# ELRS.net
KiCad netlist of a schematic drawn in Altium Designer
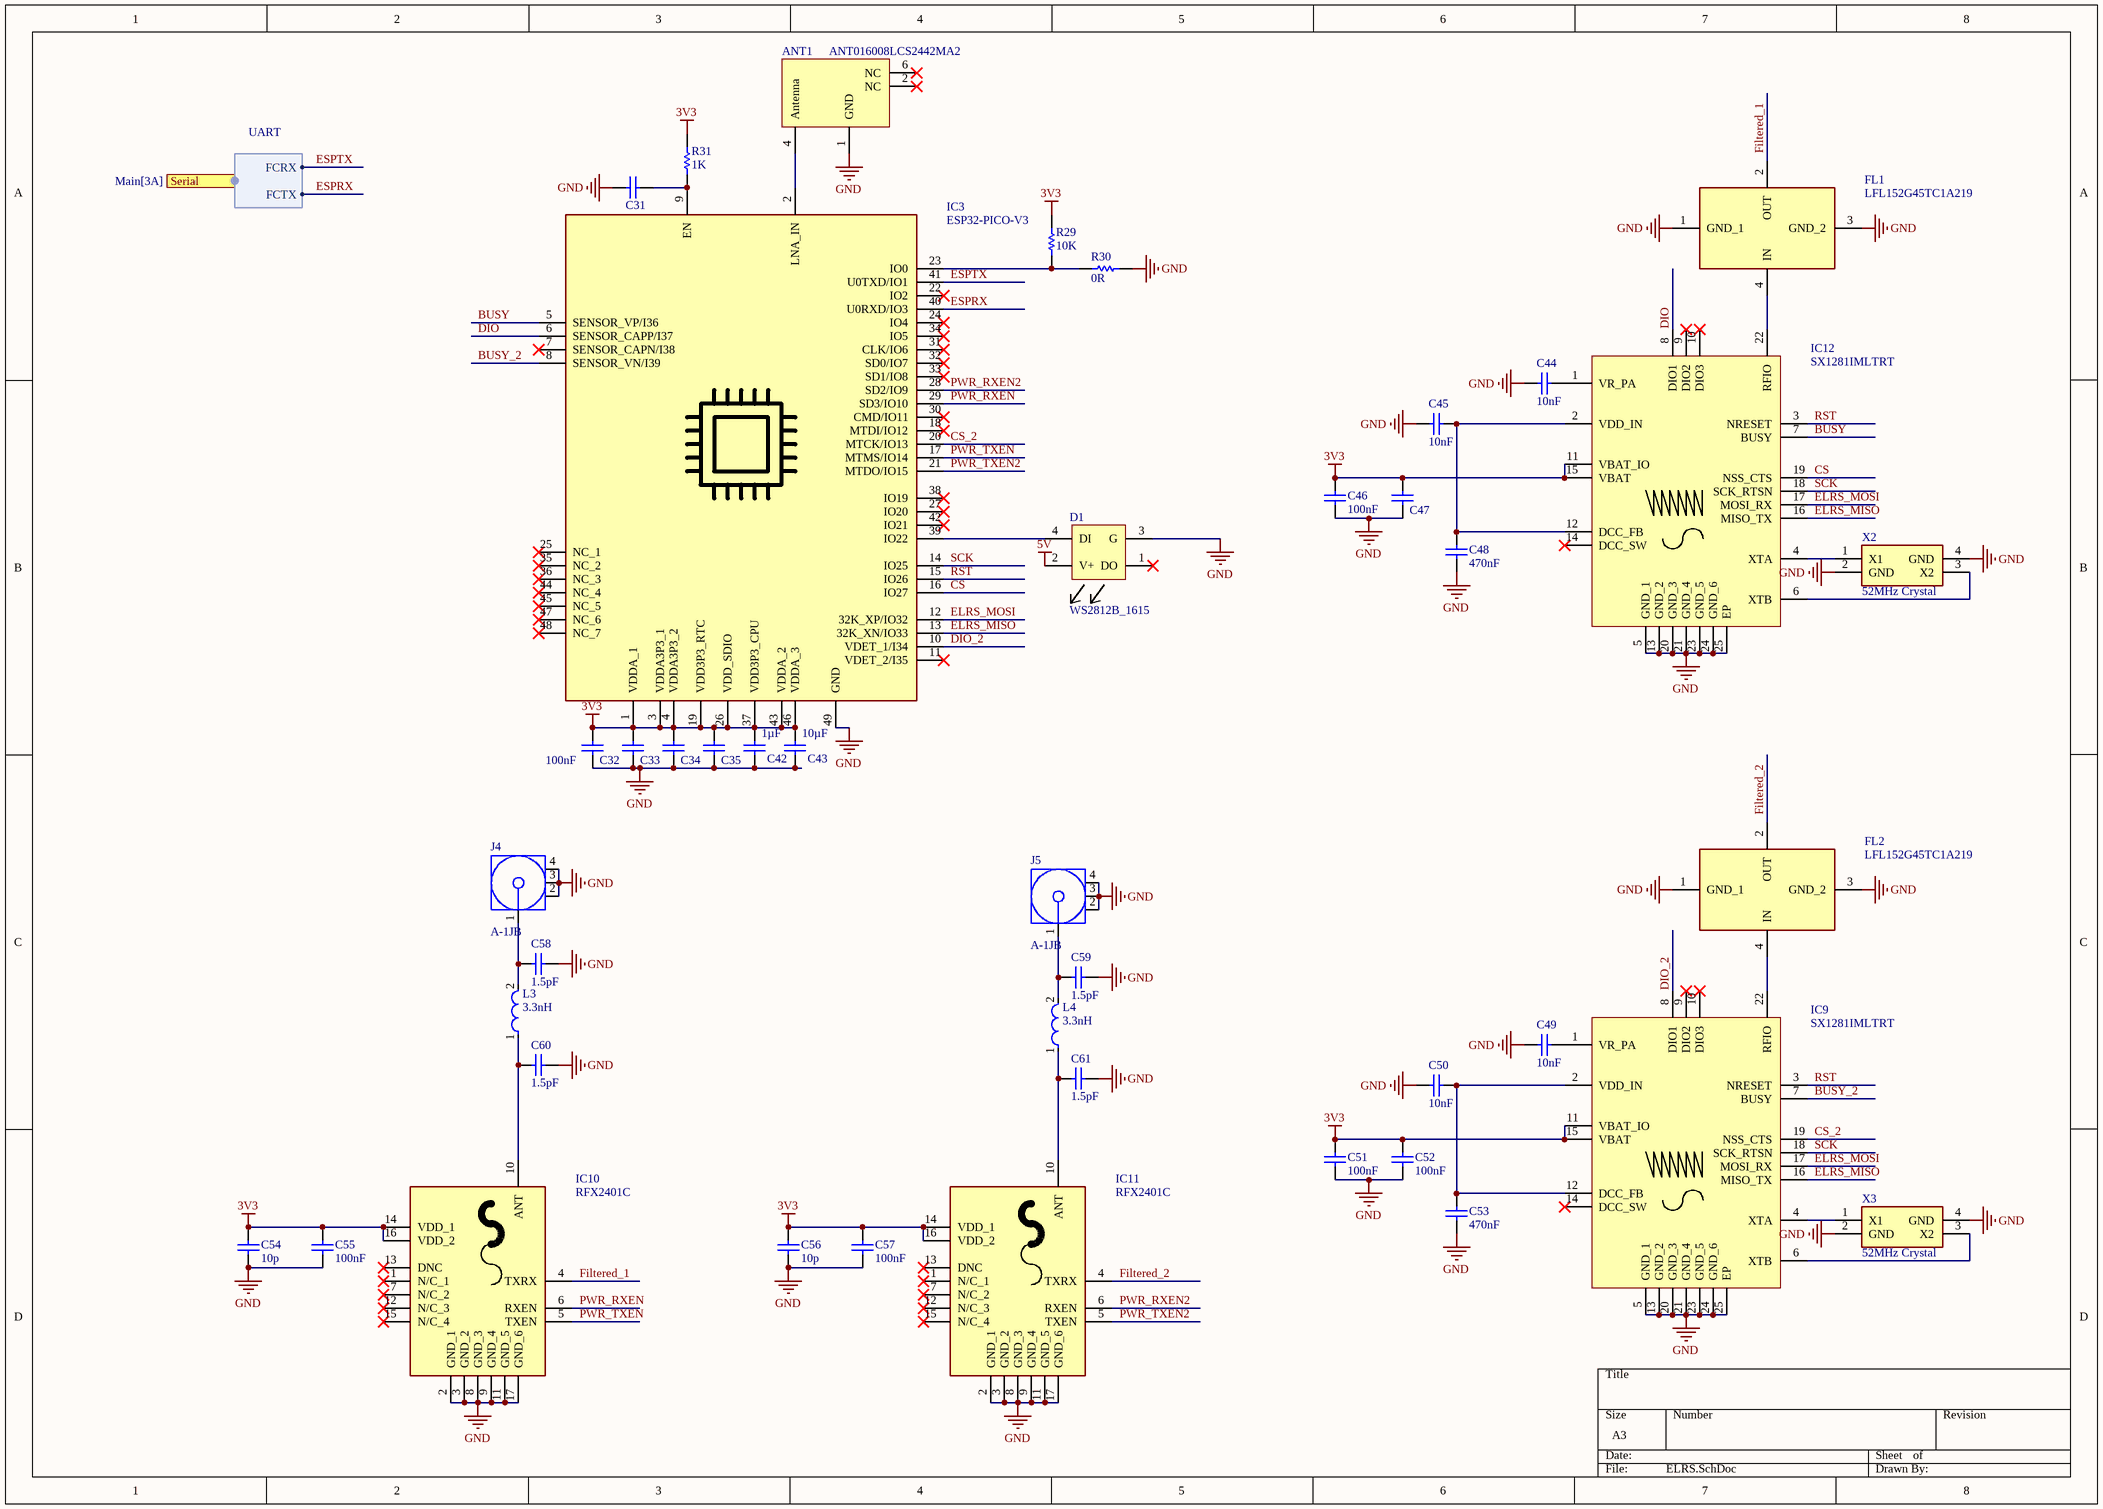
[diagram p0: ELRS.SchDoc]

(export (version "E")
  (design (tool "Eeschema 10.0.6"))
  (components
    (comp (ref "ANT1")
      (value "ANT016008LCS2442MA2")
      (footprint "Custom Components:ANT016008LCS2442MA2")
      (description "Antenna")
      (fields (field (name "MOUSER PART NUMBER") "810-ANT168LCS2442MA2"))
      (libsource (lib "Custom Components") (part "ANT016008LCS2442MA2"))
    )
    (comp (ref "C31")
      (value "100nF")
      (footprint "WCAP-CSGP_0603_L1.6W0.8H0.8_Reflow")
      (description "WCAP-CSGP Multilayer Ceramic Chip Capacitor, General Purpose, size 0603, X7R, 100nF, 50VDC")
      (fields
        (field (name "MANUFACTURER PART NUMBER") "885012206095")
        (field (name "MANUFACTURER") "Wurth Elektronik")
      )
      (libsource (lib "Altium_WCAP-CSGP (rev22f)") (part "885012206095"))
    )
    (comp (ref "C32")
      (value "100nF")
      (footprint "WCAP-CSGP_0603_L1.6W0.8H0.8_Reflow")
      (description "WCAP-CSGP Multilayer Ceramic Chip Capacitor, General Purpose, size 0603, X7R, 100nF, 50VDC")
      (fields
        (field (name "MANUFACTURER PART NUMBER") "885012206095")
        (field (name "MANUFACTURER") "Wurth Elektronik")
      )
      (libsource (lib "Altium_WCAP-CSGP (rev22f)") (part "885012206095"))
    )
    (comp (ref "C33")
      (value "100nF")
      (footprint "WCAP-CSGP_0603_L1.6W0.8H0.8_Reflow")
      (description "WCAP-CSGP Multilayer Ceramic Chip Capacitor, General Purpose, size 0603, X7R, 100nF, 50VDC")
      (fields
        (field (name "MANUFACTURER PART NUMBER") "885012206095")
        (field (name "MANUFACTURER") "Wurth Elektronik")
      )
      (libsource (lib "Altium_WCAP-CSGP (rev22f)") (part "885012206095"))
    )
    (comp (ref "C34")
      (value "100nF")
      (footprint "WCAP-CSGP_0603_L1.6W0.8H0.8_Reflow")
      (description "WCAP-CSGP Multilayer Ceramic Chip Capacitor, General Purpose, size 0603, X7R, 100nF, 50VDC")
      (fields
        (field (name "MANUFACTURER PART NUMBER") "885012206095")
        (field (name "MANUFACTURER") "Wurth Elektronik")
      )
      (libsource (lib "Altium_WCAP-CSGP (rev22f)") (part "885012206095"))
    )
    (comp (ref "C35")
      (value "100nF")
      (footprint "WCAP-CSGP_0603_L1.6W0.8H0.8_Reflow")
      (description "WCAP-CSGP Multilayer Ceramic Chip Capacitor, General Purpose, size 0603, X7R, 100nF, 50VDC")
      (fields
        (field (name "MANUFACTURER PART NUMBER") "885012206095")
        (field (name "MANUFACTURER") "Wurth Elektronik")
      )
      (libsource (lib "Altium_WCAP-CSGP (rev22f)") (part "885012206095"))
    )
    (comp (ref "C42")
      (value "1µF")
      (footprint "WCAP-CSGP_0603_L1.6W0.8H0.8_Reflow")
      (description "WCAP-CSGP Multilayer Ceramic Chip Capacitor, General Purpose, size 0603, X7R, 1µF, 25VDC")
      (fields
        (field (name "MANUFACTURER PART NUMBER") "885012206076")
        (field (name "MANUFACTURER") "Wurth Elektronik")
      )
      (libsource (lib "Altium_WCAP-CSGP (rev22f)") (part "885012206076"))
    )
    (comp (ref "C43")
      (value "10µF")
      (footprint "WCAP-CSGP_0603_L1.6W0.8H0.8_Reflow")
      (description "WCAP-CSGP Multilayer Ceramic Chip Capacitor, General Purpose, size 0603, X5R, 10µF, 25VDC")
      (fields
        (field (name "MANUFACTURER PART NUMBER") "885012106031")
        (field (name "MANUFACTURER") "Wurth Elektronik")
      )
      (libsource (lib "Altium_WCAP-CSGP (rev22f)") (part "885012106031"))
    )
    (comp (ref "C44")
      (value "10nF")
      (footprint "0402 cap")
      (libsource (lib "Custom Components") (part "Capacitor 0402 100nF"))
    )
    (comp (ref "C45")
      (value "10nF")
      (footprint "0402 cap")
      (libsource (lib "Custom Components") (part "Capacitor 0402 100nF"))
    )
    (comp (ref "C46")
      (value "100nF")
      (footprint "0402 cap")
      (libsource (lib "Custom Components") (part "Capacitor 0402 100nF"))
    )
    (comp (ref "C47")
      (value "100nF")
      (footprint "WCAP-CSGP_0603_L1.6W0.8H0.8_Reflow")
      (description "WCAP-CSGP Multilayer Ceramic Chip Capacitor, General Purpose, size 0603, X7R, 100nF, 50VDC")
      (fields
        (field (name "MANUFACTURER PART NUMBER") "885012206095")
        (field (name "MANUFACTURER") "Wurth Elektronik")
      )
      (libsource (lib "Altium_WCAP-CSGP (rev22f)") (part "885012206095"))
    )
    (comp (ref "C48")
      (value "470nF")
      (footprint "0402 cap")
      (libsource (lib "Custom Components") (part "Capacitor 0402 100nF"))
    )
    (comp (ref "C49")
      (value "10nF")
      (footprint "0402 cap")
      (libsource (lib "Custom Components") (part "Capacitor 0402 100nF"))
    )
    (comp (ref "C50")
      (value "10nF")
      (footprint "0402 cap")
      (libsource (lib "Custom Components") (part "Capacitor 0402 100nF"))
    )
    (comp (ref "C51")
      (value "100nF")
      (footprint "0402 cap")
      (libsource (lib "Custom Components") (part "Capacitor 0402 100nF"))
    )
    (comp (ref "C52")
      (value "100nF")
      (footprint "0402 cap")
      (libsource (lib "Custom Components") (part "Capacitor 0402 100nF"))
    )
    (comp (ref "C53")
      (value "470nF")
      (footprint "0402 cap")
      (libsource (lib "Custom Components") (part "Capacitor 0402 100nF"))
    )
    (comp (ref "C54")
      (value "10p")
      (footprint "0402 cap")
      (libsource (lib "Custom Components") (part "Capacitor 0402 100nF"))
    )
    (comp (ref "C55")
      (value "100nF")
      (footprint "0402 cap")
      (libsource (lib "Custom Components") (part "Capacitor 0402 100nF"))
    )
    (comp (ref "C56")
      (value "10p")
      (footprint "0402 cap")
      (libsource (lib "Custom Components") (part "Capacitor 0402 100nF"))
    )
    (comp (ref "C57")
      (value "100nF")
      (footprint "0402 cap")
      (libsource (lib "Custom Components") (part "Capacitor 0402 100nF"))
    )
    (comp (ref "C58")
      (value "1.5pF")
      (footprint "0402 cap")
      (description "CL05C1R5BB5NNNC")
      (libsource (lib "Custom Components") (part "Capacitor 0402 100nF"))
    )
    (comp (ref "C59")
      (value "1.5pF")
      (footprint "0402 cap")
      (description "CL05C1R5BB5NNNC")
      (libsource (lib "Custom Components") (part "Capacitor 0402 100nF"))
    )
    (comp (ref "C60")
      (value "1.5pF")
      (footprint "0402 cap")
      (description "CL05C1R5BB5NNNC")
      (libsource (lib "Custom Components") (part "Capacitor 0402 100nF"))
    )
    (comp (ref "C61")
      (value "1.5pF")
      (footprint "0402 cap")
      (description "CL05C1R5BB5NNNC")
      (libsource (lib "Custom Components") (part "Capacitor 0402 100nF"))
    )
    (comp (ref "D1")
      (value "WS2812B_1615")
      (footprint "WS2812B_1615")
      (description "XINGLIGHT XL-1615RGBC-WS2812B")
      (libsource (lib "Custom Components") (part "WS2812B_1615"))
    )
    (comp (ref "FL1")
      (value "LFL152G45TC1A219")
      (footprint "Custom Components:LFL152G45TC1A219")
      (description "Filter")
      (fields (field (name "MOUSER PART NUMBER") "81-LFL152G45TC1A219"))
      (libsource (lib "*") (part "LFL152G45TC1A219"))
    )
    (comp (ref "FL2")
      (value "LFL152G45TC1A219")
      (footprint "Custom Components:LFL152G45TC1A219")
      (description "Filter")
      (fields (field (name "MOUSER PART NUMBER") "81-LFL152G45TC1A219"))
      (libsource (lib "*") (part "LFL152G45TC1A219"))
    )
    (comp (ref "IC3")
      (value "ESP32-PICO-V3")
      (footprint "Custom Components:ESP32PICOV3")
      (description "Integrated Circuit")
      (fields (field (name "MOUSER PART NUMBER") "356-ESP32-PICO-V3"))
      (libsource (lib "Custom Components") (part "ESP32-PICO-V3"))
    )
    (comp (ref "IC9")
      (value "SX1281IMLTRT")
      (footprint "Custom Components:QFN50P400X400X100-25N-D")
      (description "Integrated Circuit")
      (fields (field (name "MOUSER PART NUMBER") "947-SX1281IMLTRT"))
      (libsource (lib "Custom Components") (part "SX1281IMLTRT"))
    )
    (comp (ref "IC10")
      (value "RFX2401C")
      (footprint "Custom Components:QFN50P300X300X60-17N-D")
      (description "Integrated Circuit")
      (fields (field (name "MOUSER PART NUMBER") "477-RFX2401C"))
      (libsource (lib "Custom Components") (part "RFX2401C"))
    )
    (comp (ref "IC11")
      (value "RFX2401C")
      (footprint "Custom Components:QFN50P300X300X60-17N-D")
      (description "Integrated Circuit")
      (fields (field (name "MOUSER PART NUMBER") "477-RFX2401C"))
      (libsource (lib "Custom Components") (part "RFX2401C"))
    )
    (comp (ref "IC12")
      (value "SX1281IMLTRT")
      (footprint "Custom Components:QFN50P400X400X100-25N-D")
      (description "Integrated Circuit")
      (fields (field (name "MOUSER PART NUMBER") "947-SX1281IMLTRT"))
      (libsource (lib "Custom Components") (part "SX1281IMLTRT"))
    )
    (comp (ref "J4")
      (value "A-1JB")
      (footprint "AMPH-A-1JB_V")
      (description "AMC PCB Jack, 0 to 60 GHz, 60 V, -40 to 90 degC, 4-Pin SMD, RoHS, Tape and Reel")
      (fields (field (name "TOLERANCE") "10%"))
      (libsource (lib "Altium Content Vault") (part "CN-S-3F-RF4"))
    )
    (comp (ref "J5")
      (value "A-1JB")
      (footprint "AMPH-A-1JB_V")
      (description "AMC PCB Jack, 0 to 60 GHz, 60 V, -40 to 90 degC, 4-Pin SMD, RoHS, Tape and Reel")
      (fields (field (name "TOLERANCE") "10%"))
      (libsource (lib "Altium Content Vault") (part "CN-S-3F-RF4"))
    )
    (comp (ref "L3")
      (value "3.3nH")
      (footprint "FP-LQW15AN_00-W0_6-0_1-MFG")
      (description "MLG1005S3N3BT000")
      (libsource (lib "Altium Content Vault") (part "725321dda6339637d4d059423bc1c3c"))
    )
    (comp (ref "L4")
      (value "3.3nH")
      (footprint "FP-LQW15AN_00-W0_6-0_1-MFG")
      (description "MLG1005S3N3BT000")
      (libsource (lib "Altium Content Vault") (part "725321dda6339637d4d059423bc1c3c"))
    )
    (comp (ref "R29")
      (value "10K")
      (footprint "Custom Components:0402 resistor")
      (libsource (lib "Custom Components") (part "Resistor 0402 1K"))
    )
    (comp (ref "R30")
      (value "0R")
      (footprint "Custom Components:0402 resistor")
      (libsource (lib "Custom Components") (part "Resistor 0402 1K"))
    )
    (comp (ref "R31")
      (value "1K")
      (footprint "Custom Components:0402 resistor")
      (libsource (lib "Custom Components") (part "Resistor 0402 1K"))
    )
    (comp (ref "X2")
      (value "52MHz Crystal")
      (footprint "2016 Crystal")
      (description "HCI XC21M4-52.000-F10NNHPL")
      (libsource (lib "Custom Components") (part "HCI XC21M4-52.000"))
    )
    (comp (ref "X3")
      (value "52MHz Crystal")
      (footprint "2016 Crystal")
      (description "HCI XC21M4-52.000-F10NNHPL")
      (libsource (lib "Custom Components") (part "HCI XC21M4-52.000"))
    )
  )
  (nets
    (net (code "2") (name "/BUSY") (class "Default")
      (node (ref "IC12") (pin "7") (pinfunction "BUSY_7") (pintype "passive"))
      (node (ref "IC3") (pin "5") (pinfunction "SENSOR_VP/I36_5") (pintype "passive"))
    )
    (net (code "3") (name "/BUSY_2") (class "Default")
      (node (ref "IC3") (pin "8") (pinfunction "SENSOR_VN/I39_8") (pintype "passive"))
      (node (ref "IC9") (pin "7") (pinfunction "BUSY_7") (pintype "passive"))
    )
    (net (code "4") (name "/CS") (class "Default")
      (node (ref "IC12") (pin "19") (pinfunction "NSS_CTS_19") (pintype "passive"))
      (node (ref "IC3") (pin "16") (pinfunction "IO27_16") (pintype "passive"))
    )
    (net (code "5") (name "/CS_2") (class "Default")
      (node (ref "IC3") (pin "20") (pinfunction "MTCK/IO13_20") (pintype "passive"))
      (node (ref "IC9") (pin "19") (pinfunction "NSS_CTS_19") (pintype "passive"))
    )
    (net (code "6") (name "/DIO") (class "Default")
      (node (ref "IC12") (pin "8") (pinfunction "DIO1_8") (pintype "passive"))
      (node (ref "IC3") (pin "6") (pinfunction "SENSOR_CAPP/I37_6") (pintype "passive"))
    )
    (net (code "7") (name "/DIO_2") (class "Default")
      (node (ref "IC3") (pin "10") (pinfunction "VDET_1/I34_10") (pintype "passive"))
      (node (ref "IC9") (pin "8") (pinfunction "DIO1_8") (pintype "passive"))
    )
    (net (code "8") (name "/ELRS_MISO") (class "Default")
      (node (ref "IC12") (pin "16") (pinfunction "MISO_TX_16") (pintype "passive"))
      (node (ref "IC3") (pin "13") (pinfunction "32K_XN/IO33_13") (pintype "passive"))
      (node (ref "IC9") (pin "16") (pinfunction "MISO_TX_16") (pintype "passive"))
    )
    (net (code "9") (name "/ELRS_MOSI") (class "Default")
      (node (ref "IC12") (pin "17") (pinfunction "MOSI_RX_17") (pintype "passive"))
      (node (ref "IC3") (pin "12") (pinfunction "32K_XP/IO32_12") (pintype "passive"))
      (node (ref "IC9") (pin "17") (pinfunction "MOSI_RX_17") (pintype "passive"))
    )
    (net (code "10") (name "/ESPRX") (class "Default")
      (node (ref "IC3") (pin "40") (pinfunction "U0RXD/IO3_40") (pintype "passive"))
    )
    (net (code "11") (name "/ESPTX") (class "Default")
      (node (ref "IC3") (pin "41") (pinfunction "U0TXD/IO1_41") (pintype "passive"))
    )
    (net (code "12") (name "/Filtered_1") (class "Default")
      (node (ref "FL1") (pin "2") (pinfunction "OUT_2") (pintype "passive"))
      (node (ref "IC10") (pin "4") (pinfunction "TXRX_4") (pintype "passive"))
    )
    (net (code "13") (name "/Filtered_2") (class "Default")
      (node (ref "FL2") (pin "2") (pinfunction "OUT_2") (pintype "passive"))
      (node (ref "IC11") (pin "4") (pinfunction "TXRX_4") (pintype "passive"))
    )
    (net (code "14") (name "/PWR_RXEN") (class "Default")
      (node (ref "IC10") (pin "6") (pinfunction "RXEN_6") (pintype "passive"))
      (node (ref "IC3") (pin "29") (pinfunction "SD3/IO10_29") (pintype "passive"))
    )
    (net (code "15") (name "/PWR_RXEN2") (class "Default")
      (node (ref "IC11") (pin "6") (pinfunction "RXEN_6") (pintype "passive"))
      (node (ref "IC3") (pin "28") (pinfunction "SD2/IO9_28") (pintype "passive"))
    )
    (net (code "16") (name "/PWR_TXEN") (class "Default")
      (node (ref "IC10") (pin "5") (pinfunction "TXEN_5") (pintype "passive"))
      (node (ref "IC3") (pin "17") (pinfunction "MTMS/IO14_17") (pintype "passive"))
    )
    (net (code "17") (name "/PWR_TXEN2") (class "Default")
      (node (ref "IC11") (pin "5") (pinfunction "TXEN_5") (pintype "passive"))
      (node (ref "IC3") (pin "21") (pinfunction "MTDO/IO15_21") (pintype "passive"))
    )
    (net (code "18") (name "/RST") (class "Default")
      (node (ref "IC12") (pin "3") (pinfunction "NRESET_3") (pintype "passive"))
      (node (ref "IC3") (pin "15") (pinfunction "IO26_15") (pintype "passive"))
      (node (ref "IC9") (pin "3") (pinfunction "NRESET_3") (pintype "passive"))
    )
    (net (code "19") (name "/SCK") (class "Default")
      (node (ref "IC12") (pin "18") (pinfunction "SCK_RTSN_18") (pintype "passive"))
      (node (ref "IC3") (pin "14") (pinfunction "IO25_14") (pintype "passive"))
      (node (ref "IC9") (pin "18") (pinfunction "SCK_RTSN_18") (pintype "passive"))
    )
    (net (code "21") (name "3V3") (class "Default")
      (node (ref "C32") (pin "2") (pinfunction "2_2") (pintype "passive"))
      (node (ref "C33") (pin "2") (pinfunction "2_2") (pintype "passive"))
      (node (ref "C34") (pin "2") (pinfunction "2_2") (pintype "passive"))
      (node (ref "C35") (pin "2") (pinfunction "2_2") (pintype "passive"))
      (node (ref "C42") (pin "2") (pinfunction "2_2") (pintype "passive"))
      (node (ref "C43") (pin "2") (pinfunction "2_2") (pintype "passive"))
      (node (ref "C46") (pin "2") (pinfunction "2_2") (pintype "passive"))
      (node (ref "C47") (pin "2") (pinfunction "2_2") (pintype "passive"))
      (node (ref "C51") (pin "2") (pinfunction "2_2") (pintype "passive"))
      (node (ref "C52") (pin "2") (pinfunction "2_2") (pintype "passive"))
      (node (ref "C54") (pin "2") (pinfunction "2_2") (pintype "passive"))
      (node (ref "C55") (pin "2") (pinfunction "2_2") (pintype "passive"))
      (node (ref "C56") (pin "2") (pinfunction "2_2") (pintype "passive"))
      (node (ref "C57") (pin "2") (pinfunction "2_2") (pintype "passive"))
      (node (ref "IC10") (pin "14") (pinfunction "VDD_1_14") (pintype "passive"))
      (node (ref "IC10") (pin "16") (pinfunction "VDD_2_16") (pintype "passive"))
      (node (ref "IC11") (pin "14") (pinfunction "VDD_1_14") (pintype "passive"))
      (node (ref "IC11") (pin "16") (pinfunction "VDD_2_16") (pintype "passive"))
      (node (ref "IC12") (pin "11") (pinfunction "VBAT_IO_11") (pintype "passive"))
      (node (ref "IC12") (pin "15") (pinfunction "VBAT_15") (pintype "passive"))
      (node (ref "IC3") (pin "1") (pinfunction "VDDA_1_1") (pintype "passive"))
      (node (ref "IC3") (pin "19") (pinfunction "VDD3P3_RTC_19") (pintype "passive"))
      (node (ref "IC3") (pin "26") (pinfunction "VDD_SDIO_26") (pintype "passive"))
      (node (ref "IC3") (pin "3") (pinfunction "VDDA3P3_1_3") (pintype "passive"))
      (node (ref "IC3") (pin "37") (pinfunction "VDD3P3_CPU_37") (pintype "passive"))
      (node (ref "IC3") (pin "4") (pinfunction "VDDA3P3_2_4") (pintype "passive"))
      (node (ref "IC3") (pin "43") (pinfunction "VDDA_2_43") (pintype "passive"))
      (node (ref "IC3") (pin "46") (pinfunction "VDDA_3_46") (pintype "passive"))
      (node (ref "IC9") (pin "11") (pinfunction "VBAT_IO_11") (pintype "passive"))
      (node (ref "IC9") (pin "15") (pinfunction "VBAT_15") (pintype "passive"))
      (node (ref "R29") (pin "2") (pinfunction "2_2") (pintype "passive"))
      (node (ref "R31") (pin "2") (pinfunction "2_2") (pintype "passive"))
    )
    (net (code "22") (name "5V") (class "Default")
      (node (ref "D1") (pin "2") (pinfunction "V+_2") (pintype "passive"))
    )
    (net (code "23") (name "GND") (class "Default")
      (node (ref "ANT1") (pin "1") (pinfunction "GND_1") (pintype "passive"))
      (node (ref "C31") (pin "2") (pinfunction "2_2") (pintype "passive"))
      (node (ref "C32") (pin "1") (pinfunction "1_1") (pintype "passive"))
      (node (ref "C33") (pin "1") (pinfunction "1_1") (pintype "passive"))
      (node (ref "C34") (pin "1") (pinfunction "1_1") (pintype "passive"))
      (node (ref "C35") (pin "1") (pinfunction "1_1") (pintype "passive"))
      (node (ref "C42") (pin "1") (pinfunction "1_1") (pintype "passive"))
      (node (ref "C43") (pin "1") (pinfunction "1_1") (pintype "passive"))
      (node (ref "C44") (pin "1") (pinfunction "1_1") (pintype "passive"))
      (node (ref "C45") (pin "1") (pinfunction "1_1") (pintype "passive"))
      (node (ref "C46") (pin "1") (pinfunction "1_1") (pintype "passive"))
      (node (ref "C47") (pin "1") (pinfunction "1_1") (pintype "passive"))
      (node (ref "C48") (pin "1") (pinfunction "1_1") (pintype "passive"))
      (node (ref "C49") (pin "1") (pinfunction "1_1") (pintype "passive"))
      (node (ref "C50") (pin "1") (pinfunction "1_1") (pintype "passive"))
      (node (ref "C51") (pin "1") (pinfunction "1_1") (pintype "passive"))
      (node (ref "C52") (pin "1") (pinfunction "1_1") (pintype "passive"))
      (node (ref "C53") (pin "1") (pinfunction "1_1") (pintype "passive"))
      (node (ref "C54") (pin "1") (pinfunction "1_1") (pintype "passive"))
      (node (ref "C55") (pin "1") (pinfunction "1_1") (pintype "passive"))
      (node (ref "C56") (pin "1") (pinfunction "1_1") (pintype "passive"))
      (node (ref "C57") (pin "1") (pinfunction "1_1") (pintype "passive"))
      (node (ref "C58") (pin "2") (pinfunction "2_2") (pintype "passive"))
      (node (ref "C59") (pin "2") (pinfunction "2_2") (pintype "passive"))
      (node (ref "C60") (pin "2") (pinfunction "2_2") (pintype "passive"))
      (node (ref "C61") (pin "2") (pinfunction "2_2") (pintype "passive"))
      (node (ref "D1") (pin "3") (pinfunction "G_3") (pintype "passive"))
      (node (ref "FL1") (pin "1") (pinfunction "GND_1_1") (pintype "passive"))
      (node (ref "FL1") (pin "3") (pinfunction "GND_2_3") (pintype "passive"))
      (node (ref "FL2") (pin "1") (pinfunction "GND_1_1") (pintype "passive"))
      (node (ref "FL2") (pin "3") (pinfunction "GND_2_3") (pintype "passive"))
      (node (ref "IC10") (pin "11") (pinfunction "GND_5_11") (pintype "passive"))
      (node (ref "IC10") (pin "17") (pinfunction "GND_6_17") (pintype "passive"))
      (node (ref "IC10") (pin "2") (pinfunction "GND_1_2") (pintype "passive"))
      (node (ref "IC10") (pin "3") (pinfunction "GND_2_3") (pintype "passive"))
      (node (ref "IC10") (pin "8") (pinfunction "GND_3_8") (pintype "passive"))
      (node (ref "IC10") (pin "9") (pinfunction "GND_4_9") (pintype "passive"))
      (node (ref "IC11") (pin "11") (pinfunction "GND_5_11") (pintype "passive"))
      (node (ref "IC11") (pin "17") (pinfunction "GND_6_17") (pintype "passive"))
      (node (ref "IC11") (pin "2") (pinfunction "GND_1_2") (pintype "passive"))
      (node (ref "IC11") (pin "3") (pinfunction "GND_2_3") (pintype "passive"))
      (node (ref "IC11") (pin "8") (pinfunction "GND_3_8") (pintype "passive"))
      (node (ref "IC11") (pin "9") (pinfunction "GND_4_9") (pintype "passive"))
      (node (ref "IC12") (pin "13") (pinfunction "GND_2_13") (pintype "passive"))
      (node (ref "IC12") (pin "20") (pinfunction "GND_3_20") (pintype "passive"))
      (node (ref "IC12") (pin "21") (pinfunction "GND_4_21") (pintype "passive"))
      (node (ref "IC12") (pin "23") (pinfunction "GND_5_23") (pintype "passive"))
      (node (ref "IC12") (pin "24") (pinfunction "GND_6_24") (pintype "passive"))
      (node (ref "IC12") (pin "25") (pinfunction "EP_25") (pintype "passive"))
      (node (ref "IC12") (pin "5") (pinfunction "GND_1_5") (pintype "passive"))
      (node (ref "IC3") (pin "49") (pinfunction "GND_49") (pintype "passive"))
      (node (ref "IC9") (pin "13") (pinfunction "GND_2_13") (pintype "passive"))
      (node (ref "IC9") (pin "20") (pinfunction "GND_3_20") (pintype "passive"))
      (node (ref "IC9") (pin "21") (pinfunction "GND_4_21") (pintype "passive"))
      (node (ref "IC9") (pin "23") (pinfunction "GND_5_23") (pintype "passive"))
      (node (ref "IC9") (pin "24") (pinfunction "GND_6_24") (pintype "passive"))
      (node (ref "IC9") (pin "25") (pinfunction "EP_25") (pintype "passive"))
      (node (ref "IC9") (pin "5") (pinfunction "GND_1_5") (pintype "passive"))
      (node (ref "J4") (pin "2") (pinfunction "2_2") (pintype "passive"))
      (node (ref "J4") (pin "3") (pinfunction "3_3") (pintype "passive"))
      (node (ref "J4") (pin "4") (pinfunction "4_4") (pintype "passive"))
      (node (ref "J5") (pin "2") (pinfunction "2_2") (pintype "passive"))
      (node (ref "J5") (pin "3") (pinfunction "3_3") (pintype "passive"))
      (node (ref "J5") (pin "4") (pinfunction "4_4") (pintype "passive"))
      (node (ref "R30") (pin "2") (pinfunction "2_2") (pintype "passive"))
      (node (ref "X2") (pin "2") (pinfunction "GND_2") (pintype "passive"))
      (node (ref "X2") (pin "4") (pinfunction "GND_4") (pintype "passive"))
      (node (ref "X3") (pin "2") (pinfunction "GND_2") (pintype "passive"))
      (node (ref "X3") (pin "4") (pinfunction "GND_4") (pintype "passive"))
    )
    (net (code "24") (name "Net-(ANT1-Antenna)") (class "Default")
      (node (ref "ANT1") (pin "4") (pinfunction "Antenna_4") (pintype "passive"))
      (node (ref "IC3") (pin "2") (pinfunction "LNA_IN_2") (pintype "passive"))
    )
    (net (code "25") (name "Net-(C58-Pad1)") (class "Default")
      (node (ref "C58") (pin "1") (pinfunction "1_1") (pintype "passive"))
      (node (ref "J4") (pin "1") (pinfunction "1_1") (pintype "passive"))
      (node (ref "L3") (pin "2") (pinfunction "2_2") (pintype "passive"))
    )
    (net (code "26") (name "Net-(C59-Pad1)") (class "Default")
      (node (ref "C59") (pin "1") (pinfunction "1_1") (pintype "passive"))
      (node (ref "J5") (pin "1") (pinfunction "1_1") (pintype "passive"))
      (node (ref "L4") (pin "2") (pinfunction "2_2") (pintype "passive"))
    )
    (net (code "27") (name "Net-(D1-DI)") (class "Default")
      (node (ref "D1") (pin "4") (pinfunction "DI_4") (pintype "passive"))
      (node (ref "IC3") (pin "39") (pinfunction "IO22_39") (pintype "passive"))
    )
    (net (code "28") (name "Net-(FL1-IN)") (class "Default")
      (node (ref "FL1") (pin "4") (pinfunction "IN_4") (pintype "passive"))
      (node (ref "IC12") (pin "22") (pinfunction "RFIO_22") (pintype "passive"))
    )
    (net (code "29") (name "Net-(FL2-IN)") (class "Default")
      (node (ref "FL2") (pin "4") (pinfunction "IN_4") (pintype "passive"))
      (node (ref "IC9") (pin "22") (pinfunction "RFIO_22") (pintype "passive"))
    )
    (net (code "30") (name "Net-(IC3-EN)") (class "Default")
      (node (ref "C31") (pin "1") (pinfunction "1_1") (pintype "passive"))
      (node (ref "IC3") (pin "9") (pinfunction "EN_9") (pintype "passive"))
      (node (ref "R31") (pin "1") (pinfunction "1_1") (pintype "passive"))
    )
    (net (code "31") (name "Net-(IC3-IO0)") (class "Default")
      (node (ref "IC3") (pin "23") (pinfunction "IO0_23") (pintype "passive"))
      (node (ref "R29") (pin "1") (pinfunction "1_1") (pintype "passive"))
      (node (ref "R30") (pin "1") (pinfunction "1_1") (pintype "passive"))
    )
    (net (code "32") (name "Net-(IC9-DCC_FB)") (class "Default")
      (node (ref "C50") (pin "2") (pinfunction "2_2") (pintype "passive"))
      (node (ref "C53") (pin "2") (pinfunction "2_2") (pintype "passive"))
      (node (ref "IC9") (pin "12") (pinfunction "DCC_FB_12") (pintype "passive"))
      (node (ref "IC9") (pin "2") (pinfunction "VDD_IN_2") (pintype "passive"))
    )
    (net (code "33") (name "Net-(IC9-VR_PA)") (class "Default")
      (node (ref "C49") (pin "2") (pinfunction "2_2") (pintype "passive"))
      (node (ref "IC9") (pin "1") (pinfunction "VR_PA_1") (pintype "passive"))
    )
    (net (code "34") (name "Net-(IC9-XTA)") (class "Default")
      (node (ref "IC9") (pin "4") (pinfunction "XTA_4") (pintype "passive"))
      (node (ref "X3") (pin "1") (pinfunction "X1_1") (pintype "passive"))
    )
    (net (code "35") (name "Net-(IC9-XTB)") (class "Default")
      (node (ref "IC9") (pin "6") (pinfunction "XTB_6") (pintype "passive"))
      (node (ref "X3") (pin "3") (pinfunction "X2_3") (pintype "passive"))
    )
    (net (code "36") (name "Net-(IC10-ANT)") (class "Default")
      (node (ref "C60") (pin "1") (pinfunction "1_1") (pintype "passive"))
      (node (ref "IC10") (pin "10") (pinfunction "ANT_10") (pintype "passive"))
      (node (ref "L3") (pin "1") (pinfunction "1_1") (pintype "passive"))
    )
    (net (code "37") (name "Net-(IC11-ANT)") (class "Default")
      (node (ref "C61") (pin "1") (pinfunction "1_1") (pintype "passive"))
      (node (ref "IC11") (pin "10") (pinfunction "ANT_10") (pintype "passive"))
      (node (ref "L4") (pin "1") (pinfunction "1_1") (pintype "passive"))
    )
    (net (code "38") (name "Net-(IC12-DCC_FB)") (class "Default")
      (node (ref "C45") (pin "2") (pinfunction "2_2") (pintype "passive"))
      (node (ref "C48") (pin "2") (pinfunction "2_2") (pintype "passive"))
      (node (ref "IC12") (pin "12") (pinfunction "DCC_FB_12") (pintype "passive"))
      (node (ref "IC12") (pin "2") (pinfunction "VDD_IN_2") (pintype "passive"))
    )
    (net (code "39") (name "Net-(IC12-VR_PA)") (class "Default")
      (node (ref "C44") (pin "2") (pinfunction "2_2") (pintype "passive"))
      (node (ref "IC12") (pin "1") (pinfunction "VR_PA_1") (pintype "passive"))
    )
    (net (code "40") (name "Net-(IC12-XTA)") (class "Default")
      (node (ref "IC12") (pin "4") (pinfunction "XTA_4") (pintype "passive"))
      (node (ref "X2") (pin "1") (pinfunction "X1_1") (pintype "passive"))
    )
    (net (code "41") (name "Net-(IC12-XTB)") (class "Default")
      (node (ref "IC12") (pin "6") (pinfunction "XTB_6") (pintype "passive"))
      (node (ref "X2") (pin "3") (pinfunction "X2_3") (pintype "passive"))
    )
    (net (code "42") (name "unconnected-(ANT1-NC-Pad2)") (class "Default")
      (node (ref "ANT1") (pin "2") (pinfunction "NC_2") (pintype "passive+no_connect"))
    )
    (net (code "43") (name "unconnected-(ANT1-NC-Pad6)") (class "Default")
      (node (ref "ANT1") (pin "6") (pinfunction "NC_6") (pintype "passive+no_connect"))
    )
    (net (code "44") (name "unconnected-(D1-DO-Pad1)") (class "Default")
      (node (ref "D1") (pin "1") (pinfunction "DO_1") (pintype "passive+no_connect"))
    )
    (net (code "45") (name "unconnected-(IC3-CLK{slash}IO6-Pad31)") (class "Default")
      (node (ref "IC3") (pin "31") (pinfunction "CLK/IO6_31") (pintype "passive+no_connect"))
    )
    (net (code "46") (name "unconnected-(IC3-CMD{slash}IO11-Pad30)") (class "Default")
      (node (ref "IC3") (pin "30") (pinfunction "CMD/IO11_30") (pintype "passive+no_connect"))
    )
    (net (code "47") (name "unconnected-(IC3-IO2-Pad22)") (class "Default")
      (node (ref "IC3") (pin "22") (pinfunction "IO2_22") (pintype "passive+no_connect"))
    )
    (net (code "48") (name "unconnected-(IC3-IO4-Pad24)") (class "Default")
      (node (ref "IC3") (pin "24") (pinfunction "IO4_24") (pintype "passive+no_connect"))
    )
    (net (code "49") (name "unconnected-(IC3-IO5-Pad34)") (class "Default")
      (node (ref "IC3") (pin "34") (pinfunction "IO5_34") (pintype "passive+no_connect"))
    )
    (net (code "50") (name "unconnected-(IC3-IO19-Pad38)") (class "Default")
      (node (ref "IC3") (pin "38") (pinfunction "IO19_38") (pintype "passive+no_connect"))
    )
    (net (code "51") (name "unconnected-(IC3-IO20-Pad27)") (class "Default")
      (node (ref "IC3") (pin "27") (pinfunction "IO20_27") (pintype "passive+no_connect"))
    )
    (net (code "52") (name "unconnected-(IC3-IO21-Pad42)") (class "Default")
      (node (ref "IC3") (pin "42") (pinfunction "IO21_42") (pintype "passive+no_connect"))
    )
    (net (code "53") (name "unconnected-(IC3-MTDI{slash}IO12-Pad18)") (class "Default")
      (node (ref "IC3") (pin "18") (pinfunction "MTDI/IO12_18") (pintype "passive+no_connect"))
    )
    (net (code "54") (name "unconnected-(IC3-NC_1-Pad25)") (class "Default")
      (node (ref "IC3") (pin "25") (pinfunction "NC_1_25") (pintype "passive+no_connect"))
    )
    (net (code "55") (name "unconnected-(IC3-NC_2-Pad35)") (class "Default")
      (node (ref "IC3") (pin "35") (pinfunction "NC_2_35") (pintype "passive+no_connect"))
    )
    (net (code "56") (name "unconnected-(IC3-NC_3-Pad36)") (class "Default")
      (node (ref "IC3") (pin "36") (pinfunction "NC_3_36") (pintype "passive+no_connect"))
    )
    (net (code "57") (name "unconnected-(IC3-NC_4-Pad44)") (class "Default")
      (node (ref "IC3") (pin "44") (pinfunction "NC_4_44") (pintype "passive+no_connect"))
    )
    (net (code "58") (name "unconnected-(IC3-NC_5-Pad45)") (class "Default")
      (node (ref "IC3") (pin "45") (pinfunction "NC_5_45") (pintype "passive+no_connect"))
    )
    (net (code "59") (name "unconnected-(IC3-NC_6-Pad47)") (class "Default")
      (node (ref "IC3") (pin "47") (pinfunction "NC_6_47") (pintype "passive+no_connect"))
    )
    (net (code "60") (name "unconnected-(IC3-NC_7-Pad48)") (class "Default")
      (node (ref "IC3") (pin "48") (pinfunction "NC_7_48") (pintype "passive+no_connect"))
    )
    (net (code "61") (name "unconnected-(IC3-SD0{slash}IO7-Pad32)") (class "Default")
      (node (ref "IC3") (pin "32") (pinfunction "SD0/IO7_32") (pintype "passive+no_connect"))
    )
    (net (code "62") (name "unconnected-(IC3-SD1{slash}IO8-Pad33)") (class "Default")
      (node (ref "IC3") (pin "33") (pinfunction "SD1/IO8_33") (pintype "passive+no_connect"))
    )
    (net (code "63") (name "unconnected-(IC3-SENSOR_CAPN{slash}I38-Pad7)") (class "Default")
      (node (ref "IC3") (pin "7") (pinfunction "SENSOR_CAPN/I38_7") (pintype "passive+no_connect"))
    )
    (net (code "64") (name "unconnected-(IC3-VDET_2{slash}I35-Pad11)") (class "Default")
      (node (ref "IC3") (pin "11") (pinfunction "VDET_2/I35_11") (pintype "passive+no_connect"))
    )
    (net (code "65") (name "unconnected-(IC9-DCC_SW-Pad14)") (class "Default")
      (node (ref "IC9") (pin "14") (pinfunction "DCC_SW_14") (pintype "passive+no_connect"))
    )
    (net (code "66") (name "unconnected-(IC9-DIO2-Pad9)") (class "Default")
      (node (ref "IC9") (pin "9") (pinfunction "DIO2_9") (pintype "passive+no_connect"))
    )
    (net (code "67") (name "unconnected-(IC9-DIO3-Pad10)") (class "Default")
      (node (ref "IC9") (pin "10") (pinfunction "DIO3_10") (pintype "passive+no_connect"))
    )
    (net (code "68") (name "unconnected-(IC10-DNC-Pad13)") (class "Default")
      (node (ref "IC10") (pin "13") (pinfunction "DNC_13") (pintype "passive+no_connect"))
    )
    (net (code "69") (name "unconnected-(IC10-N{slash}C_1-Pad1)") (class "Default")
      (node (ref "IC10") (pin "1") (pinfunction "N/C_1_1") (pintype "passive+no_connect"))
    )
    (net (code "70") (name "unconnected-(IC10-N{slash}C_2-Pad7)") (class "Default")
      (node (ref "IC10") (pin "7") (pinfunction "N/C_2_7") (pintype "passive+no_connect"))
    )
    (net (code "71") (name "unconnected-(IC10-N{slash}C_3-Pad12)") (class "Default")
      (node (ref "IC10") (pin "12") (pinfunction "N/C_3_12") (pintype "passive+no_connect"))
    )
    (net (code "72") (name "unconnected-(IC10-N{slash}C_4-Pad15)") (class "Default")
      (node (ref "IC10") (pin "15") (pinfunction "N/C_4_15") (pintype "passive+no_connect"))
    )
    (net (code "73") (name "unconnected-(IC11-DNC-Pad13)") (class "Default")
      (node (ref "IC11") (pin "13") (pinfunction "DNC_13") (pintype "passive+no_connect"))
    )
    (net (code "74") (name "unconnected-(IC11-N{slash}C_1-Pad1)") (class "Default")
      (node (ref "IC11") (pin "1") (pinfunction "N/C_1_1") (pintype "passive+no_connect"))
    )
    (net (code "75") (name "unconnected-(IC11-N{slash}C_2-Pad7)") (class "Default")
      (node (ref "IC11") (pin "7") (pinfunction "N/C_2_7") (pintype "passive+no_connect"))
    )
    (net (code "76") (name "unconnected-(IC11-N{slash}C_3-Pad12)") (class "Default")
      (node (ref "IC11") (pin "12") (pinfunction "N/C_3_12") (pintype "passive+no_connect"))
    )
    (net (code "77") (name "unconnected-(IC11-N{slash}C_4-Pad15)") (class "Default")
      (node (ref "IC11") (pin "15") (pinfunction "N/C_4_15") (pintype "passive+no_connect"))
    )
    (net (code "78") (name "unconnected-(IC12-DCC_SW-Pad14)") (class "Default")
      (node (ref "IC12") (pin "14") (pinfunction "DCC_SW_14") (pintype "passive+no_connect"))
    )
    (net (code "79") (name "unconnected-(IC12-DIO2-Pad9)") (class "Default")
      (node (ref "IC12") (pin "9") (pinfunction "DIO2_9") (pintype "passive+no_connect"))
    )
    (net (code "80") (name "unconnected-(IC12-DIO3-Pad10)") (class "Default")
      (node (ref "IC12") (pin "10") (pinfunction "DIO3_10") (pintype "passive+no_connect"))
    )
  )
)
